# AnySensePro.net
KiCad netlist of a schematic drawn in EAGLE
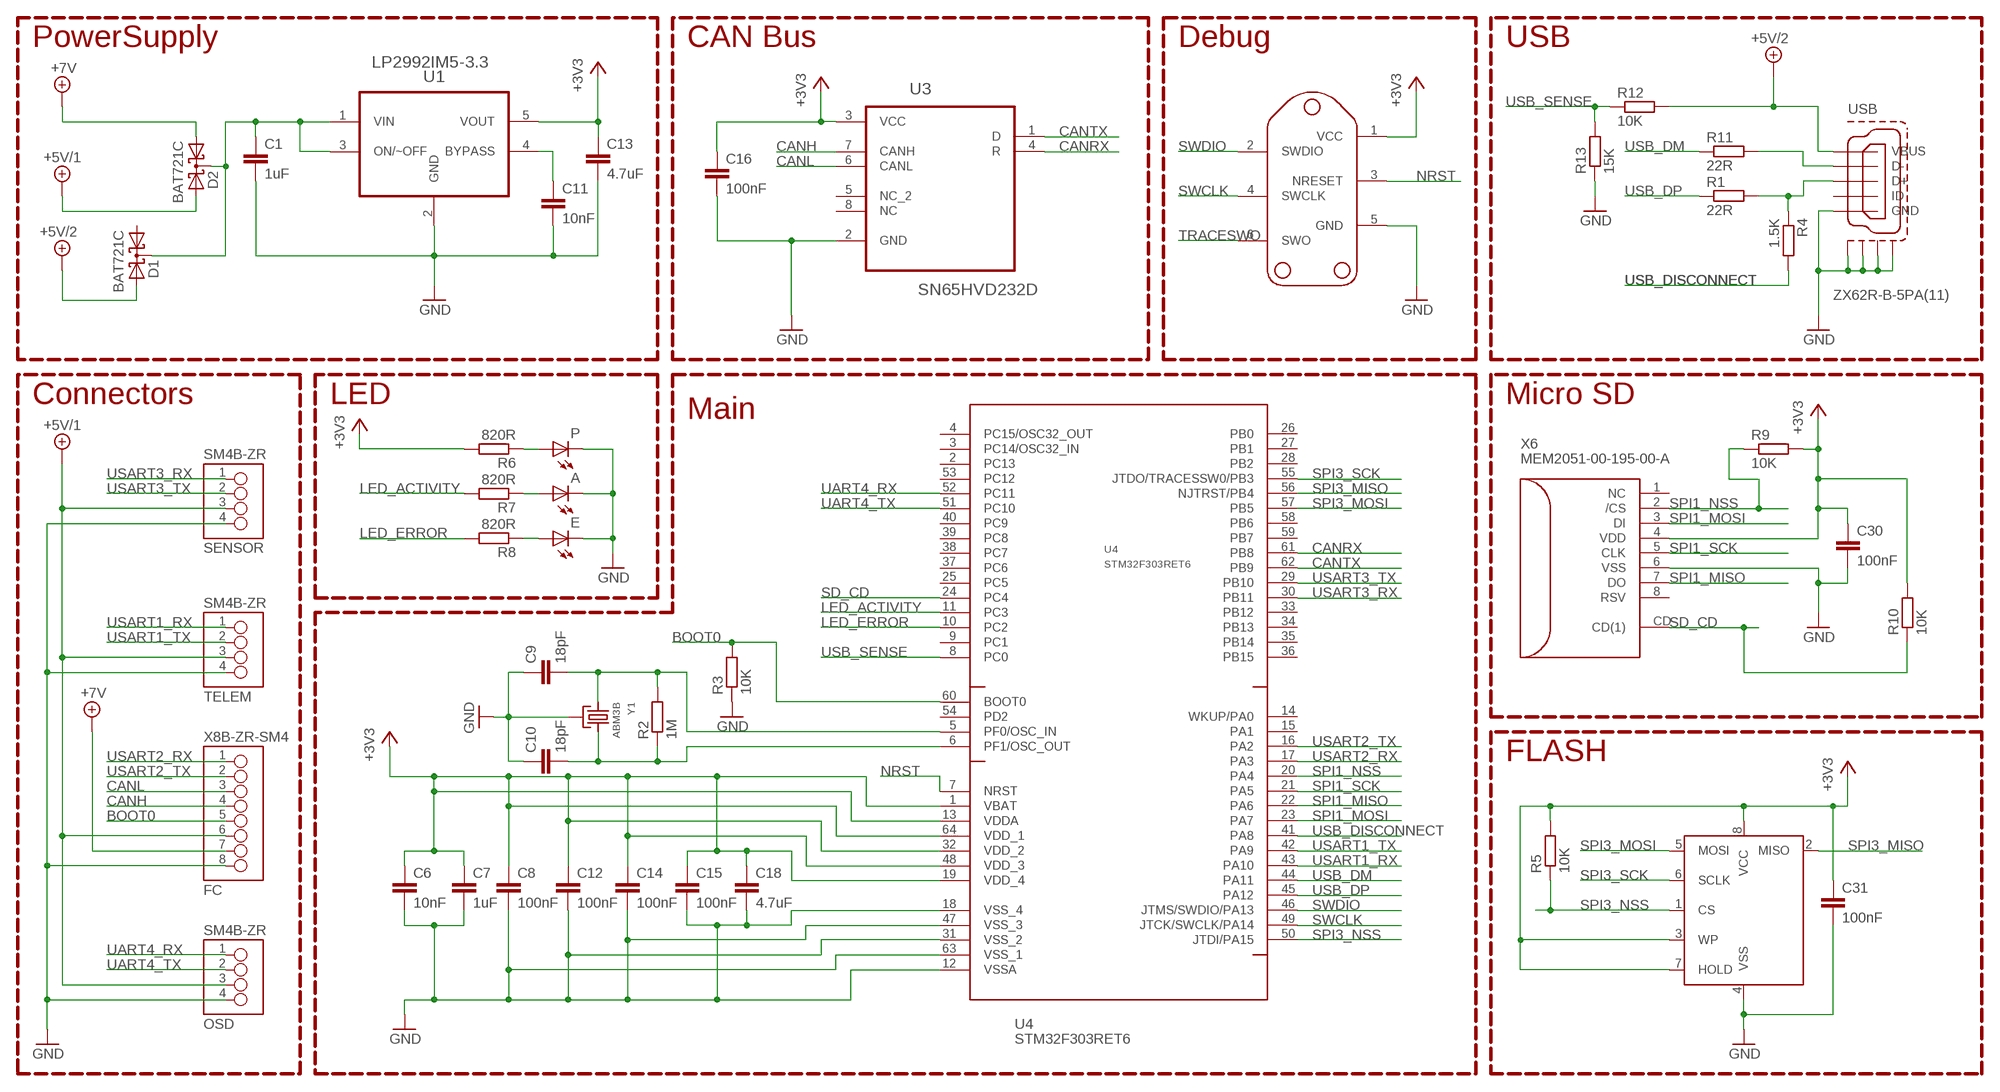
[diagram p0: schematic, sheet 1]

(export (version "E")
  (design (tool "Eeschema 10.0.6"))
  (components
    (comp (ref "A")
      (value "LEDCHIP-LED0603")
      (footprint "eagle-import:CHIP-LED0603")
      (libsource (lib "eagle-import") (part "LEDCHIP-LED0603"))
    )
    (comp (ref "C1")
      (value "1uF")
      (footprint "eagle-import:C0603K")
      (libsource (lib "eagle-import") (part "C-EUC0603K"))
    )
    (comp (ref "C6")
      (value "10nF")
      (footprint "eagle-import:C0402K")
      (libsource (lib "eagle-import") (part "C-EUC0402K"))
    )
    (comp (ref "C7")
      (value "1uF")
      (footprint "eagle-import:C0402K")
      (libsource (lib "eagle-import") (part "C-EUC0402K"))
    )
    (comp (ref "C8")
      (value "100nF")
      (footprint "eagle-import:C0402K")
      (libsource (lib "eagle-import") (part "C-EUC0402K"))
    )
    (comp (ref "C9")
      (value "18pF")
      (footprint "eagle-import:C0402K")
      (libsource (lib "eagle-import") (part "C-EUC0402K"))
    )
    (comp (ref "C10")
      (value "18pF")
      (footprint "eagle-import:C0402K")
      (libsource (lib "eagle-import") (part "C-EUC0402K"))
    )
    (comp (ref "C11")
      (value "10nF")
      (footprint "eagle-import:C0402K")
      (libsource (lib "eagle-import") (part "C-EUC0402K"))
    )
    (comp (ref "C12")
      (value "100nF")
      (footprint "eagle-import:C0402K")
      (libsource (lib "eagle-import") (part "C-EUC0402K"))
    )
    (comp (ref "C13")
      (value "4.7uF")
      (footprint "eagle-import:C0603K")
      (libsource (lib "eagle-import") (part "C-EUC0603K"))
    )
    (comp (ref "C14")
      (value "100nF")
      (footprint "eagle-import:C0402K")
      (libsource (lib "eagle-import") (part "C-EUC0402K"))
    )
    (comp (ref "C15")
      (value "100nF")
      (footprint "eagle-import:C0402K")
      (libsource (lib "eagle-import") (part "C-EUC0402K"))
    )
    (comp (ref "C16")
      (value "100nF")
      (footprint "eagle-import:C0402K")
      (libsource (lib "eagle-import") (part "C-EUC0402K"))
    )
    (comp (ref "C18")
      (value "4.7uF")
      (footprint "eagle-import:C0603K")
      (libsource (lib "eagle-import") (part "C-EUC0603K"))
    )
    (comp (ref "C30")
      (value "100nF")
      (footprint "eagle-import:C0402K")
      (libsource (lib "eagle-import") (part "C-EUC0402K"))
    )
    (comp (ref "C31")
      (value "100nF")
      (footprint "eagle-import:C0402K")
      (libsource (lib "eagle-import") (part "C-EUC0402K"))
    )
    (comp (ref "D1")
      (value "BAT721C")
      (footprint "eagle-import:SOT23")
      (libsource (lib "eagle-import") (part "BAT721C"))
    )
    (comp (ref "D2")
      (value "BAT721C")
      (footprint "eagle-import:SOT23")
      (libsource (lib "eagle-import") (part "BAT721C"))
    )
    (comp (ref "E")
      (value "LEDCHIP-LED0603")
      (footprint "eagle-import:CHIP-LED0603")
      (libsource (lib "eagle-import") (part "LEDCHIP-LED0603"))
    )
    (comp (ref "FC")
      (value "X8B-ZR-SM4")
      (footprint "eagle-import:S8B-ZR-SM4")
      (libsource (lib "eagle-import") (part "X8B-ZR-?SM4"))
    )
    (comp (ref "OSD")
      (value "SM4B-ZR")
      (footprint "eagle-import:S4B-ZR-SM4")
      (libsource (lib "eagle-import") (part "?4B-ZRSM"))
    )
    (comp (ref "P")
      (value "LEDCHIP-LED0603")
      (footprint "eagle-import:CHIP-LED0603")
      (libsource (lib "eagle-import") (part "LEDCHIP-LED0603"))
    )
    (comp (ref "R1")
      (value "22R")
      (footprint "eagle-import:R0402")
      (libsource (lib "eagle-import") (part "R-EU_R0402"))
    )
    (comp (ref "R2")
      (value "1M")
      (footprint "eagle-import:R0402")
      (libsource (lib "eagle-import") (part "R-EU_R0402"))
    )
    (comp (ref "R3")
      (value "10K")
      (footprint "eagle-import:R0402")
      (libsource (lib "eagle-import") (part "R-EU_R0402"))
    )
    (comp (ref "R4")
      (value "1.5K")
      (footprint "eagle-import:R0402")
      (libsource (lib "eagle-import") (part "R-EU_R0402"))
    )
    (comp (ref "R5")
      (value "10K")
      (footprint "eagle-import:R0402")
      (libsource (lib "eagle-import") (part "R-EU_R0402"))
    )
    (comp (ref "R6")
      (value "820R")
      (footprint "eagle-import:R0402")
      (libsource (lib "eagle-import") (part "R-EU_R0402"))
    )
    (comp (ref "R7")
      (value "820R")
      (footprint "eagle-import:R0402")
      (libsource (lib "eagle-import") (part "R-EU_R0402"))
    )
    (comp (ref "R8")
      (value "820R")
      (footprint "eagle-import:R0402")
      (libsource (lib "eagle-import") (part "R-EU_R0402"))
    )
    (comp (ref "R9")
      (value "10K")
      (footprint "eagle-import:R0402")
      (libsource (lib "eagle-import") (part "R-EU_R0402"))
    )
    (comp (ref "R10")
      (value "10K")
      (footprint "eagle-import:R0402")
      (libsource (lib "eagle-import") (part "R-EU_R0402"))
    )
    (comp (ref "R11")
      (value "22R")
      (footprint "eagle-import:R0402")
      (libsource (lib "eagle-import") (part "R-EU_R0402"))
    )
    (comp (ref "R12")
      (value "10K")
      (footprint "eagle-import:R0402")
      (libsource (lib "eagle-import") (part "R-EU_R0402"))
    )
    (comp (ref "R13")
      (value "15K")
      (footprint "eagle-import:R0402")
      (libsource (lib "eagle-import") (part "R-EU_R0402"))
    )
    (comp (ref "SENSOR")
      (value "SM4B-ZR")
      (footprint "eagle-import:S4B-ZR-SM4")
      (libsource (lib "eagle-import") (part "?4B-ZRSM"))
    )
    (comp (ref "TELEM")
      (value "SM4B-ZR")
      (footprint "eagle-import:S4B-ZR-SM4")
      (libsource (lib "eagle-import") (part "?4B-ZRSM"))
    )
    (comp (ref "U1")
      (value "LP2992IM5-3.3")
      (footprint "eagle-import:SOT-23")
      (libsource (lib "eagle-import") (part "LP2992IM5-3.3"))
    )
    (comp (ref "U3")
      (value "SN65HVD232D")
      (footprint "eagle-import:SOIC127P600X175-8N")
      (libsource (lib "eagle-import") (part "SN65HVD232D"))
    )
    (comp (ref "U4")
      (value "STM32F303RET6")
      (footprint "eagle-import:LQFP64")
      (libsource (lib "eagle-import") (part "STM32F303RET6"))
    )
    (comp (ref "U6")
      (value "M25P16VMN6P")
      (footprint "eagle-import:M25P16")
      (libsource (lib "eagle-import") (part "M25P16VMN6P"))
    )
    (comp (ref "USB")
      (value "ZX62R-B-5PA(11)")
      (footprint "eagle-import:ZX62R-B-5PA(11)")
      (libsource (lib "eagle-import") (part "ZX62R-B-5?PA(11)"))
    )
    (comp (ref "X6")
      (value "MEM2051-00-195-00-A")
      (footprint "eagle-import:MEM2051")
      (libsource (lib "eagle-import") (part "MEM2051-00-195-00-A"))
    )
    (comp (ref "X7")
      (value "TC2030-IDC-NL")
      (footprint "eagle-import:TC2030-IDC")
      (libsource (lib "eagle-import") (part "TC2030-IDC-NL"))
    )
    (comp (ref "Y1")
      (value "ABM3B")
      (footprint "eagle-import:5X3.2MM")
      (libsource (lib "eagle-import") (part "ABM3B-8.000MHZ-B2-T"))
    )
  )
  (nets
    (net (code "1") (name "+3V3") (class "Default")
      (node (ref "C12") (pin "1") (pinfunction "1_1") (pintype "passive"))
      (node (ref "C13") (pin "1") (pinfunction "1_1") (pintype "passive"))
      (node (ref "C14") (pin "1") (pinfunction "1_1") (pintype "passive"))
      (node (ref "C15") (pin "1") (pinfunction "1_1") (pintype "passive"))
      (node (ref "C16") (pin "1") (pinfunction "1_1") (pintype "passive"))
      (node (ref "C18") (pin "1") (pinfunction "1_1") (pintype "passive"))
      (node (ref "C30") (pin "1") (pinfunction "1_1") (pintype "passive"))
      (node (ref "C31") (pin "1") (pinfunction "1_1") (pintype "passive"))
      (node (ref "C6") (pin "1") (pinfunction "1_1") (pintype "passive"))
      (node (ref "C7") (pin "1") (pinfunction "1_1") (pintype "passive"))
      (node (ref "C8") (pin "1") (pinfunction "1_1") (pintype "passive"))
      (node (ref "R10") (pin "2") (pinfunction "2_2") (pintype "passive"))
      (node (ref "R5") (pin "2") (pinfunction "2_2") (pintype "passive"))
      (node (ref "R6") (pin "2") (pinfunction "2_2") (pintype "passive"))
      (node (ref "R9") (pin "2") (pinfunction "2_2") (pintype "passive"))
      (node (ref "U1") (pin "5") (pinfunction "VOUT_5") (pintype "output"))
      (node (ref "U3") (pin "3") (pinfunction "VCC_3") (pintype "power_in"))
      (node (ref "U4") (pin "1") (pinfunction "VBAT_1") (pintype "power_in"))
      (node (ref "U4") (pin "13") (pinfunction "VDDA_13") (pintype "power_in"))
      (node (ref "U4") (pin "19") (pinfunction "VDD_4_19") (pintype "power_in"))
      (node (ref "U4") (pin "32") (pinfunction "VDD_2_32") (pintype "power_in"))
      (node (ref "U4") (pin "48") (pinfunction "VDD_3_48") (pintype "power_in"))
      (node (ref "U4") (pin "64") (pinfunction "VDD_1_64") (pintype "power_in"))
      (node (ref "U6") (pin "3") (pinfunction "WP_3") (pintype "input"))
      (node (ref "U6") (pin "7") (pinfunction "HOLD_7") (pintype "input"))
      (node (ref "U6") (pin "8") (pinfunction "VCC_8") (pintype "power_in"))
      (node (ref "X6") (pin "4") (pinfunction "VDD_4") (pintype "bidirectional"))
      (node (ref "X7") (pin "1") (pinfunction "VCC_1") (pintype "bidirectional"))
    )
    (net (code "2") (name "+5V{slash}1") (class "Default")
      (node (ref "D2") (pin "2") (pinfunction "A2_2") (pintype "passive"))
      (node (ref "FC") (pin "6") (pinfunction "6_6") (pintype "bidirectional"))
      (node (ref "OSD") (pin "3") (pinfunction "3_3") (pintype "bidirectional"))
      (node (ref "SENSOR") (pin "3") (pinfunction "3_3") (pintype "bidirectional"))
      (node (ref "TELEM") (pin "3") (pinfunction "3_3") (pintype "bidirectional"))
    )
    (net (code "3") (name "+5V{slash}2") (class "Default")
      (node (ref "D1") (pin "2") (pinfunction "A2_2") (pintype "passive"))
      (node (ref "R12") (pin "2") (pinfunction "2_2") (pintype "passive"))
      (node (ref "USB") (pin "1") (pinfunction "VBUS_1") (pintype "input"))
    )
    (net (code "4") (name "+7V") (class "Default")
      (node (ref "D2") (pin "1") (pinfunction "A1_1") (pintype "passive"))
      (node (ref "FC") (pin "7") (pinfunction "7_7") (pintype "bidirectional"))
    )
    (net (code "5") (name "/BOOT0") (class "Default")
      (node (ref "FC") (pin "5") (pinfunction "5_5") (pintype "bidirectional"))
      (node (ref "R3") (pin "2") (pinfunction "2_2") (pintype "passive"))
      (node (ref "U4") (pin "60") (pinfunction "BOOT0_60") (pintype "bidirectional"))
    )
    (net (code "6") (name "/CANH") (class "Default")
      (node (ref "FC") (pin "4") (pinfunction "4_4") (pintype "bidirectional"))
      (node (ref "U3") (pin "7") (pinfunction "CANH_7") (pintype "output"))
    )
    (net (code "7") (name "/CANL") (class "Default")
      (node (ref "FC") (pin "3") (pinfunction "3_3") (pintype "bidirectional"))
      (node (ref "U3") (pin "6") (pinfunction "CANL_6") (pintype "output"))
    )
    (net (code "8") (name "/CANRX") (class "Default")
      (node (ref "U3") (pin "4") (pinfunction "R_4") (pintype "output"))
      (node (ref "U4") (pin "61") (pinfunction "PB8_61") (pintype "bidirectional"))
    )
    (net (code "9") (name "/CANTX") (class "Default")
      (node (ref "U3") (pin "1") (pinfunction "D_1") (pintype "input"))
      (node (ref "U4") (pin "62") (pinfunction "PB9_62") (pintype "bidirectional"))
    )
    (net (code "10") (name "/LED_ACTIVITY") (class "Default")
      (node (ref "R7") (pin "2") (pinfunction "2_2") (pintype "passive"))
      (node (ref "U4") (pin "11") (pinfunction "PC3_11") (pintype "bidirectional"))
    )
    (net (code "11") (name "/LED_ERROR") (class "Default")
      (node (ref "R8") (pin "2") (pinfunction "2_2") (pintype "passive"))
      (node (ref "U4") (pin "10") (pinfunction "PC2_10") (pintype "bidirectional"))
    )
    (net (code "12") (name "/NRST") (class "Default")
      (node (ref "U4") (pin "7") (pinfunction "NRST_7") (pintype "power_in"))
      (node (ref "X7") (pin "3") (pinfunction "NRESET_3") (pintype "bidirectional"))
    )
    (net (code "13") (name "/SD_CD") (class "Default")
      (node (ref "R10") (pin "1") (pinfunction "1_1") (pintype "passive"))
      (node (ref "U4") (pin "24") (pinfunction "PC4_24") (pintype "bidirectional"))
      (node (ref "X6") (pin "CD") (pinfunction "CD(1)_CD") (pintype "bidirectional"))
    )
    (net (code "14") (name "/SPI1_MISO") (class "Default")
      (node (ref "U4") (pin "22") (pinfunction "PA6_22") (pintype "bidirectional"))
      (node (ref "X6") (pin "7") (pinfunction "DO_7") (pintype "bidirectional"))
    )
    (net (code "15") (name "/SPI1_MOSI") (class "Default")
      (node (ref "U4") (pin "23") (pinfunction "PA7_23") (pintype "bidirectional"))
      (node (ref "X6") (pin "3") (pinfunction "DI_3") (pintype "bidirectional"))
    )
    (net (code "16") (name "/SPI1_NSS") (class "Default")
      (node (ref "R9") (pin "1") (pinfunction "1_1") (pintype "passive"))
      (node (ref "U4") (pin "20") (pinfunction "PA4_20") (pintype "bidirectional"))
      (node (ref "X6") (pin "2") (pinfunction "/CS_2") (pintype "bidirectional"))
    )
    (net (code "17") (name "/SPI1_SCK") (class "Default")
      (node (ref "U4") (pin "21") (pinfunction "PA5_21") (pintype "bidirectional"))
      (node (ref "X6") (pin "5") (pinfunction "CLK_5") (pintype "bidirectional"))
    )
    (net (code "18") (name "/SPI3_MISO") (class "Default")
      (node (ref "U4") (pin "56") (pinfunction "NJTRST/PB4_56") (pintype "bidirectional"))
      (node (ref "U6") (pin "2") (pinfunction "MISO_2") (pintype "output"))
    )
    (net (code "19") (name "/SPI3_MOSI") (class "Default")
      (node (ref "U4") (pin "57") (pinfunction "PB5_57") (pintype "bidirectional"))
      (node (ref "U6") (pin "5") (pinfunction "MOSI_5") (pintype "input"))
    )
    (net (code "20") (name "/SPI3_NSS") (class "Default")
      (node (ref "R5") (pin "1") (pinfunction "1_1") (pintype "passive"))
      (node (ref "U4") (pin "50") (pinfunction "JTDI/PA15_50") (pintype "bidirectional"))
      (node (ref "U6") (pin "1") (pinfunction "CS_1") (pintype "input"))
    )
    (net (code "21") (name "/SPI3_SCK") (class "Default")
      (node (ref "U4") (pin "55") (pinfunction "JTDO/TRACESSW0/PB3_55") (pintype "bidirectional"))
      (node (ref "U6") (pin "6") (pinfunction "SCLK_6") (pintype "input"))
    )
    (net (code "22") (name "/SWCLK") (class "Default")
      (node (ref "U4") (pin "49") (pinfunction "JTCK/SWCLK/PA14_49") (pintype "bidirectional"))
      (node (ref "X7") (pin "4") (pinfunction "SWCLK_4") (pintype "bidirectional"))
    )
    (net (code "23") (name "/SWDIO") (class "Default")
      (node (ref "U4") (pin "46") (pinfunction "JTMS/SWDIO/PA13_46") (pintype "bidirectional"))
      (node (ref "X7") (pin "2") (pinfunction "SWDIO_2") (pintype "bidirectional"))
    )
    (net (code "24") (name "/TRACESWO") (class "Default")
      (node (ref "X7") (pin "6") (pinfunction "SWO_6") (pintype "bidirectional"))
    )
    (net (code "25") (name "/UART4_RX") (class "Default")
      (node (ref "OSD") (pin "1") (pinfunction "1_1") (pintype "bidirectional"))
      (node (ref "U4") (pin "52") (pinfunction "PC11_52") (pintype "bidirectional"))
    )
    (net (code "26") (name "/UART4_TX") (class "Default")
      (node (ref "OSD") (pin "2") (pinfunction "2_2") (pintype "bidirectional"))
      (node (ref "U4") (pin "51") (pinfunction "PC10_51") (pintype "bidirectional"))
    )
    (net (code "27") (name "/USART1_RX") (class "Default")
      (node (ref "TELEM") (pin "1") (pinfunction "1_1") (pintype "bidirectional"))
      (node (ref "U4") (pin "43") (pinfunction "PA10_43") (pintype "bidirectional"))
    )
    (net (code "28") (name "/USART1_TX") (class "Default")
      (node (ref "TELEM") (pin "2") (pinfunction "2_2") (pintype "bidirectional"))
      (node (ref "U4") (pin "42") (pinfunction "PA9_42") (pintype "bidirectional"))
    )
    (net (code "29") (name "/USART2_RX") (class "Default")
      (node (ref "FC") (pin "1") (pinfunction "1_1") (pintype "bidirectional"))
      (node (ref "U4") (pin "17") (pinfunction "PA3_17") (pintype "bidirectional"))
    )
    (net (code "30") (name "/USART2_TX") (class "Default")
      (node (ref "FC") (pin "2") (pinfunction "2_2") (pintype "bidirectional"))
      (node (ref "U4") (pin "16") (pinfunction "PA2_16") (pintype "bidirectional"))
    )
    (net (code "31") (name "/USART3_RX") (class "Default")
      (node (ref "SENSOR") (pin "1") (pinfunction "1_1") (pintype "bidirectional"))
      (node (ref "U4") (pin "30") (pinfunction "PB11_30") (pintype "bidirectional"))
    )
    (net (code "32") (name "/USART3_TX") (class "Default")
      (node (ref "SENSOR") (pin "2") (pinfunction "2_2") (pintype "bidirectional"))
      (node (ref "U4") (pin "29") (pinfunction "PB10_29") (pintype "bidirectional"))
    )
    (net (code "33") (name "/USB_DISCONNECT") (class "Default")
      (node (ref "R4") (pin "2") (pinfunction "2_2") (pintype "passive"))
      (node (ref "U4") (pin "41") (pinfunction "PA8_41") (pintype "bidirectional"))
    )
    (net (code "34") (name "/USB_DM") (class "Default")
      (node (ref "R11") (pin "1") (pinfunction "1_1") (pintype "passive"))
      (node (ref "U4") (pin "44") (pinfunction "PA11_44") (pintype "bidirectional"))
    )
    (net (code "35") (name "/USB_DP") (class "Default")
      (node (ref "R1") (pin "1") (pinfunction "1_1") (pintype "passive"))
      (node (ref "U4") (pin "45") (pinfunction "PA12_45") (pintype "bidirectional"))
    )
    (net (code "36") (name "/USB_SENSE") (class "Default")
      (node (ref "R12") (pin "1") (pinfunction "1_1") (pintype "passive"))
      (node (ref "R13") (pin "2") (pinfunction "2_2") (pintype "passive"))
      (node (ref "U4") (pin "8") (pinfunction "PC0_8") (pintype "bidirectional"))
    )
    (net (code "37") (name "GND") (class "Default")
      (node (ref "A") (pin "C") (pinfunction "C_C") (pintype "passive"))
      (node (ref "C1") (pin "2") (pinfunction "2_2") (pintype "passive"))
      (node (ref "C10") (pin "1") (pinfunction "1_1") (pintype "passive"))
      (node (ref "C11") (pin "2") (pinfunction "2_2") (pintype "passive"))
      (node (ref "C12") (pin "2") (pinfunction "2_2") (pintype "passive"))
      (node (ref "C13") (pin "2") (pinfunction "2_2") (pintype "passive"))
      (node (ref "C14") (pin "2") (pinfunction "2_2") (pintype "passive"))
      (node (ref "C15") (pin "2") (pinfunction "2_2") (pintype "passive"))
      (node (ref "C16") (pin "2") (pinfunction "2_2") (pintype "passive"))
      (node (ref "C18") (pin "2") (pinfunction "2_2") (pintype "passive"))
      (node (ref "C30") (pin "2") (pinfunction "2_2") (pintype "passive"))
      (node (ref "C31") (pin "2") (pinfunction "2_2") (pintype "passive"))
      (node (ref "C6") (pin "2") (pinfunction "2_2") (pintype "passive"))
      (node (ref "C7") (pin "2") (pinfunction "2_2") (pintype "passive"))
      (node (ref "C8") (pin "2") (pinfunction "2_2") (pintype "passive"))
      (node (ref "C9") (pin "1") (pinfunction "1_1") (pintype "passive"))
      (node (ref "E") (pin "C") (pinfunction "C_C") (pintype "passive"))
      (node (ref "FC") (pin "8") (pinfunction "8_8") (pintype "bidirectional"))
      (node (ref "OSD") (pin "4") (pinfunction "4_4") (pintype "bidirectional"))
      (node (ref "P") (pin "C") (pinfunction "C_C") (pintype "passive"))
      (node (ref "R13") (pin "1") (pinfunction "1_1") (pintype "passive"))
      (node (ref "R3") (pin "1") (pinfunction "1_1") (pintype "passive"))
      (node (ref "SENSOR") (pin "4") (pinfunction "4_4") (pintype "bidirectional"))
      (node (ref "TELEM") (pin "4") (pinfunction "4_4") (pintype "bidirectional"))
      (node (ref "U1") (pin "2") (pinfunction "GND_2") (pintype "passive"))
      (node (ref "U3") (pin "2") (pinfunction "GND_2") (pintype "passive"))
      (node (ref "U4") (pin "12") (pinfunction "VSSA_12") (pintype "passive"))
      (node (ref "U4") (pin "18") (pinfunction "VSS_4_18") (pintype "passive"))
      (node (ref "U4") (pin "31") (pinfunction "VSS_2_31") (pintype "passive"))
      (node (ref "U4") (pin "47") (pinfunction "VSS_3_47") (pintype "passive"))
      (node (ref "U4") (pin "63") (pinfunction "VSS_1_63") (pintype "passive"))
      (node (ref "U6") (pin "4") (pinfunction "VSS_4") (pintype "passive"))
      (node (ref "USB") (pin "5") (pinfunction "GND_5") (pintype "passive"))
      (node (ref "USB") (pin "M1") (pinfunction "S1_M1") (pintype "passive"))
      (node (ref "USB") (pin "M2") (pinfunction "S2_M2") (pintype "passive"))
      (node (ref "USB") (pin "M3") (pinfunction "S3_M3") (pintype "passive"))
      (node (ref "USB") (pin "M4") (pinfunction "S4_M4") (pintype "passive"))
      (node (ref "X6") (pin "6") (pinfunction "VSS_6") (pintype "bidirectional"))
      (node (ref "X7") (pin "5") (pinfunction "GND_5") (pintype "bidirectional"))
      (node (ref "Y1") (pin "2") (pinfunction "GND_2") (pintype "passive"))
      (node (ref "Y1") (pin "4") (pinfunction "GND_4") (pintype "passive"))
    )
    (net (code "38") (name "Net-(A-PadA)") (class "Default")
      (node (ref "A") (pin "A") (pinfunction "A_A") (pintype "passive"))
      (node (ref "R7") (pin "1") (pinfunction "1_1") (pintype "passive"))
    )
    (net (code "39") (name "Net-(D1-CC)") (class "Default")
      (node (ref "C1") (pin "1") (pinfunction "1_1") (pintype "passive"))
      (node (ref "D1") (pin "3") (pinfunction "CC_3") (pintype "passive"))
      (node (ref "D2") (pin "3") (pinfunction "CC_3") (pintype "passive"))
      (node (ref "U1") (pin "1") (pinfunction "VIN_1") (pintype "power_in"))
      (node (ref "U1") (pin "3") (pinfunction "ON/~{OFF}_3") (pintype "input"))
    )
    (net (code "40") (name "Net-(E-PadA)") (class "Default")
      (node (ref "E") (pin "A") (pinfunction "A_A") (pintype "passive"))
      (node (ref "R8") (pin "1") (pinfunction "1_1") (pintype "passive"))
    )
    (net (code "41") (name "Net-(P-PadA)") (class "Default")
      (node (ref "P") (pin "A") (pinfunction "A_A") (pintype "passive"))
      (node (ref "R6") (pin "1") (pinfunction "1_1") (pintype "passive"))
    )
    (net (code "42") (name "Net-(U1-BYPASS)") (class "Default")
      (node (ref "C11") (pin "1") (pinfunction "1_1") (pintype "passive"))
      (node (ref "U1") (pin "4") (pinfunction "BYPASS_4") (pintype "input"))
    )
    (net (code "43") (name "Net-(U4-PF0{slash}OSC_IN)") (class "Default")
      (node (ref "C9") (pin "2") (pinfunction "2_2") (pintype "passive"))
      (node (ref "R2") (pin "2") (pinfunction "2_2") (pintype "passive"))
      (node (ref "U4") (pin "5") (pinfunction "PF0/OSC_IN_5") (pintype "bidirectional"))
      (node (ref "Y1") (pin "1") (pinfunction "1_1") (pintype "passive"))
    )
    (net (code "44") (name "Net-(U4-PF1{slash}OSC_OUT)") (class "Default")
      (node (ref "C10") (pin "2") (pinfunction "2_2") (pintype "passive"))
      (node (ref "R2") (pin "1") (pinfunction "1_1") (pintype "passive"))
      (node (ref "U4") (pin "6") (pinfunction "PF1/OSC_OUT_6") (pintype "bidirectional"))
      (node (ref "Y1") (pin "3") (pinfunction "2_3") (pintype "passive"))
    )
    (net (code "45") (name "Net-(USBA-D+)") (class "Default")
      (node (ref "R1") (pin "2") (pinfunction "2_2") (pintype "passive"))
      (node (ref "R4") (pin "1") (pinfunction "1_1") (pintype "passive"))
      (node (ref "USB") (pin "3") (pinfunction "D+_3") (pintype "input"))
    )
    (net (code "46") (name "Net-(USBA-D-)") (class "Default")
      (node (ref "R11") (pin "2") (pinfunction "2_2") (pintype "passive"))
      (node (ref "USB") (pin "2") (pinfunction "D-_2") (pintype "input"))
    )
    (net (code "47") (name "unconnected-(D1-A1-Pad1)") (class "Default")
      (node (ref "D1") (pin "1") (pinfunction "A1_1") (pintype "passive"))
    )
    (net (code "48") (name "unconnected-(U3-NC-Pad8)") (class "Default")
      (node (ref "U3") (pin "8") (pinfunction "NC_8") (pintype "no_connect"))
    )
    (net (code "49") (name "unconnected-(U3-NC_2-Pad5)") (class "Default")
      (node (ref "U3") (pin "5") (pinfunction "NC_2_5") (pintype "no_connect"))
    )
    (net (code "50") (name "unconnected-(U4-PA1-Pad15)") (class "Default")
      (node (ref "U4") (pin "15") (pinfunction "PA1_15") (pintype "bidirectional"))
    )
    (net (code "51") (name "unconnected-(U4-PB0-Pad26)") (class "Default")
      (node (ref "U4") (pin "26") (pinfunction "PB0_26") (pintype "bidirectional"))
    )
    (net (code "52") (name "unconnected-(U4-PB1-Pad27)") (class "Default")
      (node (ref "U4") (pin "27") (pinfunction "PB1_27") (pintype "bidirectional"))
    )
    (net (code "53") (name "unconnected-(U4-PB2-Pad28)") (class "Default")
      (node (ref "U4") (pin "28") (pinfunction "PB2_28") (pintype "bidirectional"))
    )
    (net (code "54") (name "unconnected-(U4-PB6-Pad58)") (class "Default")
      (node (ref "U4") (pin "58") (pinfunction "PB6_58") (pintype "bidirectional"))
    )
    (net (code "55") (name "unconnected-(U4-PB7-Pad59)") (class "Default")
      (node (ref "U4") (pin "59") (pinfunction "PB7_59") (pintype "bidirectional"))
    )
    (net (code "56") (name "unconnected-(U4-PB12-Pad33)") (class "Default")
      (node (ref "U4") (pin "33") (pinfunction "PB12_33") (pintype "bidirectional"))
    )
    (net (code "57") (name "unconnected-(U4-PB13-Pad34)") (class "Default")
      (node (ref "U4") (pin "34") (pinfunction "PB13_34") (pintype "bidirectional"))
    )
    (net (code "58") (name "unconnected-(U4-PB14-Pad35)") (class "Default")
      (node (ref "U4") (pin "35") (pinfunction "PB14_35") (pintype "bidirectional"))
    )
    (net (code "59") (name "unconnected-(U4-PB15-Pad36)") (class "Default")
      (node (ref "U4") (pin "36") (pinfunction "PB15_36") (pintype "bidirectional"))
    )
    (net (code "60") (name "unconnected-(U4-PC1-Pad9)") (class "Default")
      (node (ref "U4") (pin "9") (pinfunction "PC1_9") (pintype "bidirectional"))
    )
    (net (code "61") (name "unconnected-(U4-PC5-Pad25)") (class "Default")
      (node (ref "U4") (pin "25") (pinfunction "PC5_25") (pintype "bidirectional"))
    )
    (net (code "62") (name "unconnected-(U4-PC6-Pad37)") (class "Default")
      (node (ref "U4") (pin "37") (pinfunction "PC6_37") (pintype "bidirectional"))
    )
    (net (code "63") (name "unconnected-(U4-PC7-Pad38)") (class "Default")
      (node (ref "U4") (pin "38") (pinfunction "PC7_38") (pintype "bidirectional"))
    )
    (net (code "64") (name "unconnected-(U4-PC8-Pad39)") (class "Default")
      (node (ref "U4") (pin "39") (pinfunction "PC8_39") (pintype "bidirectional"))
    )
    (net (code "65") (name "unconnected-(U4-PC9-Pad40)") (class "Default")
      (node (ref "U4") (pin "40") (pinfunction "PC9_40") (pintype "bidirectional"))
    )
    (net (code "66") (name "unconnected-(U4-PC12-Pad53)") (class "Default")
      (node (ref "U4") (pin "53") (pinfunction "PC12_53") (pintype "bidirectional"))
    )
    (net (code "67") (name "unconnected-(U4-PC13-Pad2)") (class "Default")
      (node (ref "U4") (pin "2") (pinfunction "PC13_2") (pintype "bidirectional"))
    )
    (net (code "68") (name "unconnected-(U4-PC14{slash}OSC32_IN-Pad3)") (class "Default")
      (node (ref "U4") (pin "3") (pinfunction "PC14/OSC32_IN_3") (pintype "bidirectional"))
    )
    (net (code "69") (name "unconnected-(U4-PC15{slash}OSC32_OUT-Pad4)") (class "Default")
      (node (ref "U4") (pin "4") (pinfunction "PC15/OSC32_OUT_4") (pintype "bidirectional"))
    )
    (net (code "70") (name "unconnected-(U4-PD2-Pad54)") (class "Default")
      (node (ref "U4") (pin "54") (pinfunction "PD2_54") (pintype "bidirectional"))
    )
    (net (code "71") (name "unconnected-(U4-WKUP{slash}PA0-Pad14)") (class "Default")
      (node (ref "U4") (pin "14") (pinfunction "WKUP/PA0_14") (pintype "bidirectional"))
    )
    (net (code "72") (name "unconnected-(USBA-ID-Pad4)") (class "Default")
      (node (ref "USB") (pin "4") (pinfunction "ID_4") (pintype "no_connect"))
    )
    (net (code "73") (name "unconnected-(X6-NC-Pad1)") (class "Default")
      (node (ref "X6") (pin "1") (pinfunction "NC_1") (pintype "bidirectional"))
    )
    (net (code "74") (name "unconnected-(X6-RSV-Pad8)") (class "Default")
      (node (ref "X6") (pin "8") (pinfunction "RSV_8") (pintype "bidirectional"))
    )
  )
)
